# shield_v2.net
KiCad netlist of a schematic drawn in EAGLE
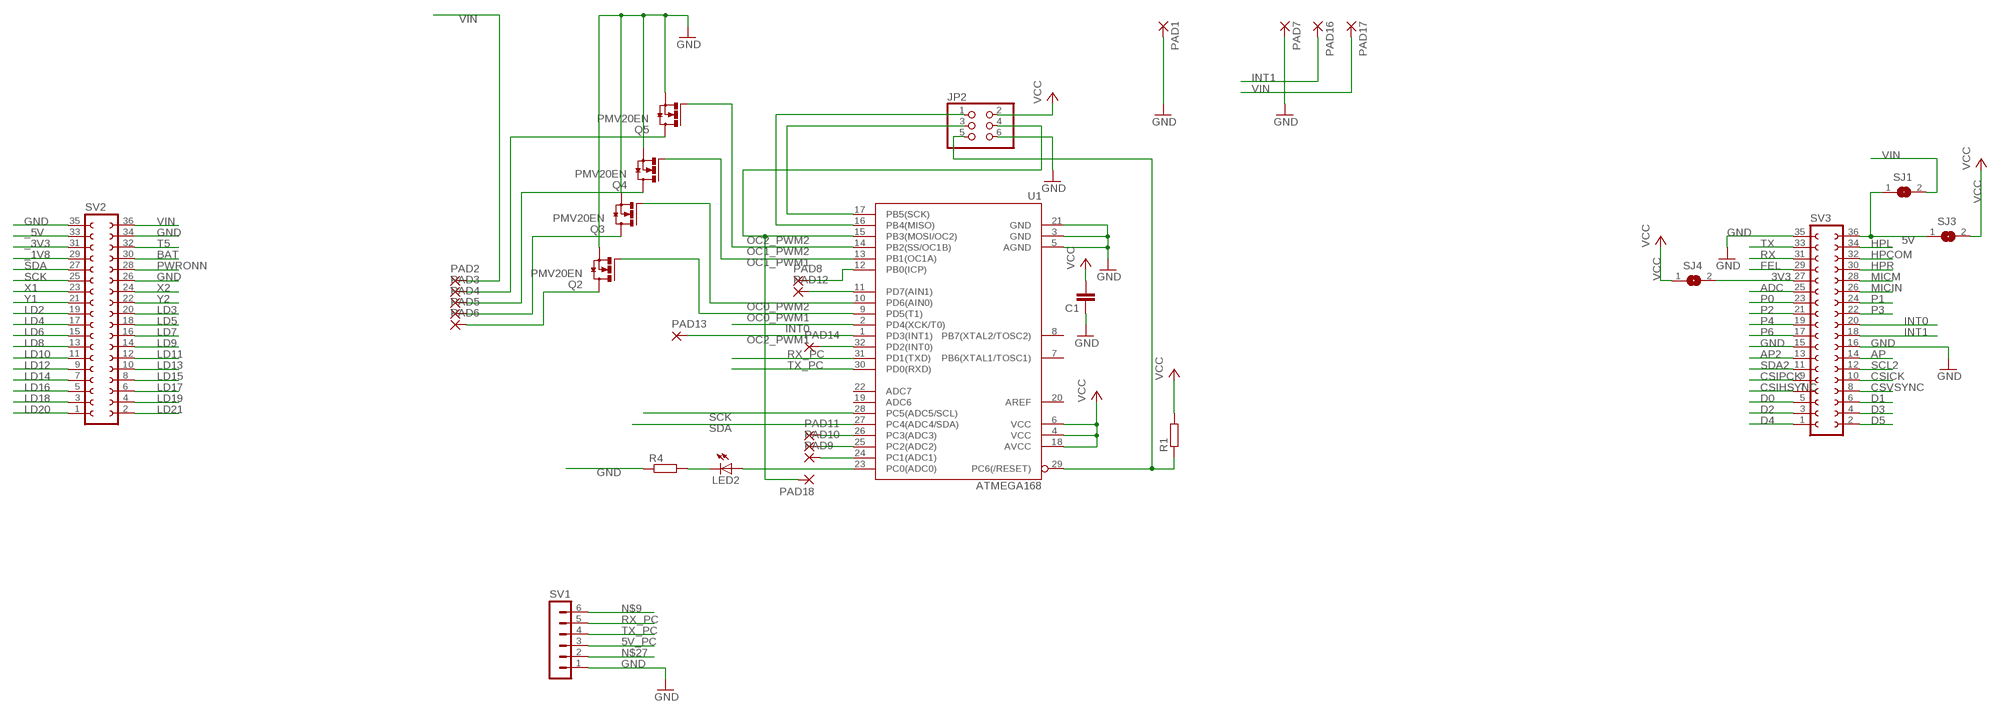
[diagram p0: schematic, sheet 1]

(export (version "E")
  (design (tool "Eeschema 10.0.6"))
  (components
    (comp (ref "C1")
      (value "C-EUC0805")
      (footprint "eagle-import:C0805")
      (libsource (lib "eagle-import") (part "C-EUC0805"))
    )
    (comp (ref "JP2")
      (value "PINHD-2X3")
      (footprint "eagle-import:2X03")
      (libsource (lib "eagle-import") (part "PINHD-2X3"))
    )
    (comp (ref "LED2")
      (value "LEDCHIP-LED0805")
      (footprint "eagle-import:CHIP-LED0805")
      (libsource (lib "eagle-import") (part "LEDCHIP-LED0805"))
    )
    (comp (ref "PAD1")
      (value "3,17/1,3")
      (footprint "eagle-import:3,17_1,3")
      (libsource (lib "eagle-import") (part "3,17/1,3"))
    )
    (comp (ref "PAD2")
      (value "3,17/1,3")
      (footprint "eagle-import:3,17_1,3")
      (libsource (lib "eagle-import") (part "3,17/1,3"))
    )
    (comp (ref "PAD3")
      (value "3,17/1,3")
      (footprint "eagle-import:3,17_1,3")
      (libsource (lib "eagle-import") (part "3,17/1,3"))
    )
    (comp (ref "PAD4")
      (value "3,17/1,3")
      (footprint "eagle-import:3,17_1,3")
      (libsource (lib "eagle-import") (part "3,17/1,3"))
    )
    (comp (ref "PAD5")
      (value "3,17/1,3")
      (footprint "eagle-import:3,17_1,3")
      (libsource (lib "eagle-import") (part "3,17/1,3"))
    )
    (comp (ref "PAD6")
      (value "3,17/1,3")
      (footprint "eagle-import:3,17_1,3")
      (libsource (lib "eagle-import") (part "3,17/1,3"))
    )
    (comp (ref "PAD7")
      (value "3,17/1,3")
      (footprint "eagle-import:3,17_1,3")
      (libsource (lib "eagle-import") (part "3,17/1,3"))
    )
    (comp (ref "PAD8")
      (value "SMD5")
      (footprint "eagle-import:SMD2,54-5,08")
      (libsource (lib "eagle-import") (part "SMD5"))
    )
    (comp (ref "PAD9")
      (value "3,17/1,3")
      (footprint "eagle-import:3,17_1,3")
      (libsource (lib "eagle-import") (part "3,17/1,3"))
    )
    (comp (ref "PAD10")
      (value "3,17/1,3")
      (footprint "eagle-import:3,17_1,3")
      (libsource (lib "eagle-import") (part "3,17/1,3"))
    )
    (comp (ref "PAD11")
      (value "3,17/1,3")
      (footprint "eagle-import:3,17_1,3")
      (libsource (lib "eagle-import") (part "3,17/1,3"))
    )
    (comp (ref "PAD12")
      (value "SMD5")
      (footprint "eagle-import:SMD2,54-5,08")
      (libsource (lib "eagle-import") (part "SMD5"))
    )
    (comp (ref "PAD13")
      (value "SMD2")
      (footprint "eagle-import:SMD1,27-2,54")
      (libsource (lib "eagle-import") (part "SMD2"))
    )
    (comp (ref "PAD14")
      (value "3,17/1,3")
      (footprint "eagle-import:3,17_1,3")
      (libsource (lib "eagle-import") (part "3,17/1,3"))
    )
    (comp (ref "PAD16")
      (value "3,17/1,3")
      (footprint "eagle-import:3,17_1,3")
      (libsource (lib "eagle-import") (part "3,17/1,3"))
    )
    (comp (ref "PAD17")
      (value "3,17/1,3")
      (footprint "eagle-import:3,17_1,3")
      (libsource (lib "eagle-import") (part "3,17/1,3"))
    )
    (comp (ref "PAD18")
      (value "3,17/1,3")
      (footprint "eagle-import:3,17_1,3")
      (libsource (lib "eagle-import") (part "3,17/1,3"))
    )
    (comp (ref "Q2")
      (value "PMV20EN")
      (footprint "eagle-import:SOT223")
      (libsource (lib "eagle-import") (part "NMOSFET_SMD_223"))
    )
    (comp (ref "Q3")
      (value "PMV20EN")
      (footprint "eagle-import:SOT223")
      (libsource (lib "eagle-import") (part "NMOSFET_SMD_223"))
    )
    (comp (ref "Q4")
      (value "PMV20EN")
      (footprint "eagle-import:SOT223")
      (libsource (lib "eagle-import") (part "NMOSFET_SMD_223"))
    )
    (comp (ref "Q5")
      (value "PMV20EN")
      (footprint "eagle-import:SOT223")
      (libsource (lib "eagle-import") (part "NMOSFET_SMD_223"))
    )
    (comp (ref "R1")
      (value "R-EU_M1206")
      (footprint "eagle-import:M1206")
      (libsource (lib "eagle-import") (part "R-EU_M1206"))
    )
    (comp (ref "R4")
      (value "R-EU_M1206")
      (footprint "eagle-import:M1206")
      (libsource (lib "eagle-import") (part "R-EU_M1206"))
    )
    (comp (ref "SJ1") (value "SJ") (footprint "eagle-import:SJ") (libsource (lib "eagle-import") (part "SJ")))
    (comp (ref "SJ3") (value "SJ") (footprint "eagle-import:SJ") (libsource (lib "eagle-import") (part "SJ")))
    (comp (ref "SJ4") (value "SJ") (footprint "eagle-import:SJ") (libsource (lib "eagle-import") (part "SJ")))
    (comp (ref "SV1")
      (value "MA06-1")
      (footprint "eagle-import:MA06-1")
      (libsource (lib "eagle-import") (part "MA06-1"))
    )
    (comp (ref "SV2")
      (value "FE18-2")
      (footprint "eagle-import:FE18-2")
      (libsource (lib "eagle-import") (part "FE18-2"))
    )
    (comp (ref "SV3")
      (value "FE18-2")
      (footprint "eagle-import:FE18-2")
      (libsource (lib "eagle-import") (part "FE18-2"))
    )
    (comp (ref "U1")
      (value "ATMEGA168")
      (footprint "eagle-import:TQFP32-08")
      (libsource (lib "eagle-import") (part "ATMEGA168"))
    )
  )
  (nets
    (net (code "1") (name "/3V3") (class "Default")
      (node (ref "SJ4") (pin "2") (pinfunction "2_2") (pintype "passive"))
      (node (ref "SV3") (pin "27") (pinfunction "27_27") (pintype "passive"))
    )
    (net (code "2") (name "/5V") (class "Default")
      (node (ref "SJ1") (pin "1") (pinfunction "1_1") (pintype "passive"))
      (node (ref "SJ3") (pin "1") (pinfunction "1_1") (pintype "passive"))
      (node (ref "SV3") (pin "36") (pinfunction "36_36") (pintype "passive"))
    )
    (net (code "3") (name "/5V_PC") (class "Default")
      (node (ref "SV1") (pin "3") (pinfunction "3_3") (pintype "passive"))
    )
    (net (code "4") (name "/ADC") (class "Default")
      (node (ref "SV3") (pin "25") (pinfunction "25_25") (pintype "passive"))
    )
    (net (code "5") (name "/AP") (class "Default")
      (node (ref "SV3") (pin "14") (pinfunction "14_14") (pintype "passive"))
    )
    (net (code "6") (name "/AP2") (class "Default")
      (node (ref "SV3") (pin "13") (pinfunction "13_13") (pintype "passive"))
    )
    (net (code "7") (name "/BAT") (class "Default")
      (node (ref "SV2") (pin "30") (pinfunction "30_30") (pintype "passive"))
    )
    (net (code "8") (name "/CSICK") (class "Default")
      (node (ref "SV3") (pin "10") (pinfunction "10_10") (pintype "passive"))
    )
    (net (code "9") (name "/CSIHSYNC") (class "Default")
      (node (ref "SV3") (pin "7") (pinfunction "7_7") (pintype "passive"))
    )
    (net (code "10") (name "/CSIPCK") (class "Default")
      (node (ref "SV3") (pin "9") (pinfunction "9_9") (pintype "passive"))
    )
    (net (code "11") (name "/CSVSYNC") (class "Default")
      (node (ref "SV3") (pin "8") (pinfunction "8_8") (pintype "passive"))
    )
    (net (code "12") (name "/D0") (class "Default")
      (node (ref "SV3") (pin "5") (pinfunction "5_5") (pintype "passive"))
    )
    (net (code "13") (name "/D1") (class "Default")
      (node (ref "SV3") (pin "6") (pinfunction "6_6") (pintype "passive"))
    )
    (net (code "14") (name "/D2") (class "Default")
      (node (ref "SV3") (pin "3") (pinfunction "3_3") (pintype "passive"))
    )
    (net (code "15") (name "/D3") (class "Default")
      (node (ref "SV3") (pin "4") (pinfunction "4_4") (pintype "passive"))
    )
    (net (code "16") (name "/D4") (class "Default")
      (node (ref "SV3") (pin "1") (pinfunction "1_1") (pintype "passive"))
    )
    (net (code "17") (name "/D5") (class "Default")
      (node (ref "SV3") (pin "2") (pinfunction "2_2") (pintype "passive"))
    )
    (net (code "18") (name "/FEL") (class "Default")
      (node (ref "SV3") (pin "29") (pinfunction "29_29") (pintype "passive"))
    )
    (net (code "19") (name "/HPCOM") (class "Default")
      (node (ref "SV3") (pin "32") (pinfunction "32_32") (pintype "passive"))
    )
    (net (code "20") (name "/HPL") (class "Default")
      (node (ref "SV3") (pin "34") (pinfunction "34_34") (pintype "passive"))
    )
    (net (code "21") (name "/HPR") (class "Default")
      (node (ref "SV3") (pin "30") (pinfunction "30_30") (pintype "passive"))
    )
    (net (code "22") (name "/INT0") (class "Default")
      (node (ref "SV3") (pin "20") (pinfunction "20_20") (pintype "passive"))
      (node (ref "U1") (pin "2") (pinfunction "PD4(XCK/T0)_2") (pintype "bidirectional"))
    )
    (net (code "23") (name "/INT1") (class "Default")
      (node (ref "PAD16") (pin "1") (pinfunction "P_1") (pintype "passive"))
      (node (ref "SV3") (pin "18") (pinfunction "18_18") (pintype "passive"))
    )
    (net (code "24") (name "/LD2") (class "Default")
      (node (ref "SV2") (pin "19") (pinfunction "19_19") (pintype "passive"))
    )
    (net (code "25") (name "/LD3") (class "Default")
      (node (ref "SV2") (pin "20") (pinfunction "20_20") (pintype "passive"))
    )
    (net (code "26") (name "/LD4") (class "Default")
      (node (ref "SV2") (pin "17") (pinfunction "17_17") (pintype "passive"))
    )
    (net (code "27") (name "/LD5") (class "Default")
      (node (ref "SV2") (pin "18") (pinfunction "18_18") (pintype "passive"))
    )
    (net (code "28") (name "/LD6") (class "Default")
      (node (ref "SV2") (pin "15") (pinfunction "15_15") (pintype "passive"))
    )
    (net (code "29") (name "/LD7") (class "Default")
      (node (ref "SV2") (pin "16") (pinfunction "16_16") (pintype "passive"))
    )
    (net (code "30") (name "/LD8") (class "Default")
      (node (ref "SV2") (pin "13") (pinfunction "13_13") (pintype "passive"))
    )
    (net (code "31") (name "/LD9") (class "Default")
      (node (ref "SV2") (pin "14") (pinfunction "14_14") (pintype "passive"))
    )
    (net (code "32") (name "/LD10") (class "Default")
      (node (ref "SV2") (pin "11") (pinfunction "11_11") (pintype "passive"))
    )
    (net (code "33") (name "/LD11") (class "Default")
      (node (ref "SV2") (pin "12") (pinfunction "12_12") (pintype "passive"))
    )
    (net (code "34") (name "/LD12") (class "Default")
      (node (ref "SV2") (pin "9") (pinfunction "9_9") (pintype "passive"))
    )
    (net (code "35") (name "/LD13") (class "Default")
      (node (ref "SV2") (pin "10") (pinfunction "10_10") (pintype "passive"))
    )
    (net (code "36") (name "/LD14") (class "Default")
      (node (ref "SV2") (pin "7") (pinfunction "7_7") (pintype "passive"))
    )
    (net (code "37") (name "/LD15") (class "Default")
      (node (ref "SV2") (pin "8") (pinfunction "8_8") (pintype "passive"))
    )
    (net (code "38") (name "/LD16") (class "Default")
      (node (ref "SV2") (pin "5") (pinfunction "5_5") (pintype "passive"))
    )
    (net (code "39") (name "/LD17") (class "Default")
      (node (ref "SV2") (pin "6") (pinfunction "6_6") (pintype "passive"))
    )
    (net (code "40") (name "/LD18") (class "Default")
      (node (ref "SV2") (pin "3") (pinfunction "3_3") (pintype "passive"))
    )
    (net (code "41") (name "/LD19") (class "Default")
      (node (ref "SV2") (pin "4") (pinfunction "4_4") (pintype "passive"))
    )
    (net (code "42") (name "/LD20") (class "Default")
      (node (ref "SV2") (pin "1") (pinfunction "1_1") (pintype "passive"))
    )
    (net (code "43") (name "/LD21") (class "Default")
      (node (ref "SV2") (pin "2") (pinfunction "2_2") (pintype "passive"))
    )
    (net (code "44") (name "/MICIN") (class "Default")
      (node (ref "SV3") (pin "26") (pinfunction "26_26") (pintype "passive"))
    )
    (net (code "45") (name "/MICM") (class "Default")
      (node (ref "SV3") (pin "28") (pinfunction "28_28") (pintype "passive"))
    )
    (net (code "46") (name "/N$9") (class "Default")
      (node (ref "SV1") (pin "6") (pinfunction "6_6") (pintype "passive"))
    )
    (net (code "47") (name "/N$27") (class "Default")
      (node (ref "SV1") (pin "2") (pinfunction "2_2") (pintype "passive"))
    )
    (net (code "48") (name "/OC0_PWM1") (class "Default")
      (node (ref "Q2") (pin "1") (pinfunction "G_1") (pintype "passive"))
      (node (ref "U1") (pin "9") (pinfunction "PD5(T1)_9") (pintype "bidirectional"))
    )
    (net (code "49") (name "/OC0_PWM2") (class "Default")
      (node (ref "Q3") (pin "1") (pinfunction "G_1") (pintype "passive"))
      (node (ref "U1") (pin "10") (pinfunction "PD6(AIN0)_10") (pintype "bidirectional"))
    )
    (net (code "50") (name "/OC1_PWM1") (class "Default")
      (node (ref "Q4") (pin "1") (pinfunction "G_1") (pintype "passive"))
      (node (ref "U1") (pin "13") (pinfunction "PB1(OC1A)_13") (pintype "bidirectional"))
    )
    (net (code "51") (name "/OC1_PWM2") (class "Default")
      (node (ref "Q5") (pin "1") (pinfunction "G_1") (pintype "passive"))
      (node (ref "U1") (pin "14") (pinfunction "PB2(SS/OC1B)_14") (pintype "bidirectional"))
    )
    (net (code "52") (name "/OC2_PWM1") (class "Default")
      (node (ref "PAD13") (pin "1") (pinfunction "P_1") (pintype "passive"))
      (node (ref "U1") (pin "1") (pinfunction "PD3(INT1)_1") (pintype "bidirectional"))
    )
    (net (code "53") (name "/OC2_PWM2") (class "Default")
      (node (ref "JP2") (pin "4") (pinfunction "4_4") (pintype "passive"))
      (node (ref "PAD18") (pin "1") (pinfunction "P_1") (pintype "passive"))
      (node (ref "U1") (pin "15") (pinfunction "PB3(MOSI/OC2)_15") (pintype "bidirectional"))
    )
    (net (code "54") (name "/P0") (class "Default")
      (node (ref "SV3") (pin "23") (pinfunction "23_23") (pintype "passive"))
    )
    (net (code "55") (name "/P1") (class "Default")
      (node (ref "SV3") (pin "24") (pinfunction "24_24") (pintype "passive"))
    )
    (net (code "56") (name "/P2") (class "Default")
      (node (ref "SV3") (pin "21") (pinfunction "21_21") (pintype "passive"))
    )
    (net (code "57") (name "/P3") (class "Default")
      (node (ref "SV3") (pin "22") (pinfunction "22_22") (pintype "passive"))
    )
    (net (code "58") (name "/P4") (class "Default")
      (node (ref "SV3") (pin "19") (pinfunction "19_19") (pintype "passive"))
    )
    (net (code "59") (name "/P6") (class "Default")
      (node (ref "SV3") (pin "17") (pinfunction "17_17") (pintype "passive"))
    )
    (net (code "60") (name "/PWRONN") (class "Default")
      (node (ref "SV2") (pin "28") (pinfunction "28_28") (pintype "passive"))
    )
    (net (code "61") (name "/RX") (class "Default")
      (node (ref "SV3") (pin "31") (pinfunction "31_31") (pintype "passive"))
    )
    (net (code "62") (name "/RX_PC") (class "Default")
      (node (ref "SV1") (pin "5") (pinfunction "5_5") (pintype "passive"))
      (node (ref "U1") (pin "31") (pinfunction "PD1(TXD)_31") (pintype "bidirectional"))
    )
    (net (code "63") (name "/SCK") (class "Default")
      (node (ref "SV2") (pin "25") (pinfunction "25_25") (pintype "passive"))
      (node (ref "U1") (pin "28") (pinfunction "PC5(ADC5/SCL)_28") (pintype "bidirectional"))
    )
    (net (code "64") (name "/SCL2") (class "Default")
      (node (ref "SV3") (pin "12") (pinfunction "12_12") (pintype "passive"))
    )
    (net (code "65") (name "/SDA") (class "Default")
      (node (ref "SV2") (pin "27") (pinfunction "27_27") (pintype "passive"))
      (node (ref "U1") (pin "27") (pinfunction "PC4(ADC4/SDA)_27") (pintype "bidirectional"))
    )
    (net (code "66") (name "/SDA2") (class "Default")
      (node (ref "SV3") (pin "11") (pinfunction "11_11") (pintype "passive"))
    )
    (net (code "67") (name "/T5") (class "Default")
      (node (ref "SV2") (pin "32") (pinfunction "32_32") (pintype "passive"))
    )
    (net (code "68") (name "/TX") (class "Default")
      (node (ref "SV3") (pin "33") (pinfunction "33_33") (pintype "passive"))
    )
    (net (code "69") (name "/TX_PC") (class "Default")
      (node (ref "SV1") (pin "4") (pinfunction "4_4") (pintype "passive"))
      (node (ref "U1") (pin "30") (pinfunction "PD0(RXD)_30") (pintype "bidirectional"))
    )
    (net (code "70") (name "/VIN") (class "Default")
      (node (ref "PAD17") (pin "1") (pinfunction "P_1") (pintype "passive"))
      (node (ref "PAD2") (pin "1") (pinfunction "P_1") (pintype "passive"))
      (node (ref "SJ1") (pin "2") (pinfunction "2_2") (pintype "passive"))
      (node (ref "SV2") (pin "36") (pinfunction "36_36") (pintype "passive"))
    )
    (net (code "71") (name "/X1") (class "Default")
      (node (ref "SV2") (pin "23") (pinfunction "23_23") (pintype "passive"))
    )
    (net (code "72") (name "/X2") (class "Default")
      (node (ref "SV2") (pin "24") (pinfunction "24_24") (pintype "passive"))
    )
    (net (code "73") (name "/Y1") (class "Default")
      (node (ref "SV2") (pin "21") (pinfunction "21_21") (pintype "passive"))
    )
    (net (code "74") (name "/Y2") (class "Default")
      (node (ref "SV2") (pin "22") (pinfunction "22_22") (pintype "passive"))
    )
    (net (code "75") (name "/_1V8") (class "Default")
      (node (ref "SV2") (pin "29") (pinfunction "29_29") (pintype "passive"))
    )
    (net (code "76") (name "/_3V3") (class "Default")
      (node (ref "SV2") (pin "31") (pinfunction "31_31") (pintype "passive"))
    )
    (net (code "77") (name "/_5V") (class "Default")
      (node (ref "SV2") (pin "33") (pinfunction "33_33") (pintype "passive"))
    )
    (net (code "78") (name "GND") (class "Default")
      (node (ref "C1") (pin "1") (pinfunction "1_1") (pintype "passive"))
      (node (ref "JP2") (pin "6") (pinfunction "6_6") (pintype "passive"))
      (node (ref "PAD1") (pin "1") (pinfunction "P_1") (pintype "passive"))
      (node (ref "PAD7") (pin "1") (pinfunction "P_1") (pintype "passive"))
      (node (ref "Q2") (pin "3") (pinfunction "S_3") (pintype "passive"))
      (node (ref "Q3") (pin "3") (pinfunction "S_3") (pintype "passive"))
      (node (ref "Q4") (pin "3") (pinfunction "S_3") (pintype "passive"))
      (node (ref "Q5") (pin "3") (pinfunction "S_3") (pintype "passive"))
      (node (ref "R4") (pin "1") (pinfunction "1_1") (pintype "passive"))
      (node (ref "SV1") (pin "1") (pinfunction "1_1") (pintype "passive"))
      (node (ref "SV2") (pin "26") (pinfunction "26_26") (pintype "passive"))
      (node (ref "SV2") (pin "34") (pinfunction "34_34") (pintype "passive"))
      (node (ref "SV2") (pin "35") (pinfunction "35_35") (pintype "passive"))
      (node (ref "SV3") (pin "15") (pinfunction "15_15") (pintype "passive"))
      (node (ref "SV3") (pin "16") (pinfunction "16_16") (pintype "passive"))
      (node (ref "SV3") (pin "35") (pinfunction "35_35") (pintype "passive"))
      (node (ref "U1") (pin "21") (pinfunction "GND_21") (pintype "bidirectional"))
      (node (ref "U1") (pin "3") (pinfunction "GND_3") (pintype "bidirectional"))
      (node (ref "U1") (pin "5") (pinfunction "AGND_5") (pintype "bidirectional"))
    )
    (net (code "79") (name "Net-(LED2-PadC)") (class "Default")
      (node (ref "LED2") (pin "C") (pinfunction "C_C") (pintype "passive"))
      (node (ref "R4") (pin "2") (pinfunction "2_2") (pintype "passive"))
    )
    (net (code "80") (name "Net-(PAD3-P)") (class "Default")
      (node (ref "PAD3") (pin "1") (pinfunction "P_1") (pintype "passive"))
      (node (ref "Q5") (pin "2") (pinfunction "D_2") (pintype "passive"))
      (node (ref "Q5") (pin "4") (pinfunction "D_4") (pintype "passive"))
    )
    (net (code "81") (name "Net-(PAD4-P)") (class "Default")
      (node (ref "PAD4") (pin "1") (pinfunction "P_1") (pintype "passive"))
      (node (ref "Q4") (pin "2") (pinfunction "D_2") (pintype "passive"))
      (node (ref "Q4") (pin "4") (pinfunction "D_4") (pintype "passive"))
    )
    (net (code "82") (name "Net-(PAD5-P)") (class "Default")
      (node (ref "PAD5") (pin "1") (pinfunction "P_1") (pintype "passive"))
      (node (ref "Q3") (pin "2") (pinfunction "D_2") (pintype "passive"))
      (node (ref "Q3") (pin "4") (pinfunction "D_4") (pintype "passive"))
    )
    (net (code "83") (name "Net-(PAD6-P)") (class "Default")
      (node (ref "PAD6") (pin "1") (pinfunction "P_1") (pintype "passive"))
      (node (ref "Q2") (pin "2") (pinfunction "D_2") (pintype "passive"))
      (node (ref "Q2") (pin "4") (pinfunction "D_4") (pintype "passive"))
    )
    (net (code "84") (name "Net-(PAD8-P)") (class "Default")
      (node (ref "PAD8") (pin "1") (pinfunction "P_1") (pintype "passive"))
      (node (ref "U1") (pin "12") (pinfunction "PB0(ICP)_12") (pintype "bidirectional"))
    )
    (net (code "85") (name "Net-(PAD9-P)") (class "Default")
      (node (ref "PAD9") (pin "1") (pinfunction "P_1") (pintype "passive"))
      (node (ref "U1") (pin "24") (pinfunction "PC1(ADC1)_24") (pintype "bidirectional"))
    )
    (net (code "86") (name "Net-(PAD10-P)") (class "Default")
      (node (ref "PAD10") (pin "1") (pinfunction "P_1") (pintype "passive"))
      (node (ref "U1") (pin "25") (pinfunction "PC2(ADC2)_25") (pintype "bidirectional"))
    )
    (net (code "87") (name "Net-(PAD11-P)") (class "Default")
      (node (ref "PAD11") (pin "1") (pinfunction "P_1") (pintype "passive"))
      (node (ref "U1") (pin "26") (pinfunction "PC3(ADC3)_26") (pintype "bidirectional"))
    )
    (net (code "88") (name "Net-(PAD12-P)") (class "Default")
      (node (ref "PAD12") (pin "1") (pinfunction "P_1") (pintype "passive"))
      (node (ref "U1") (pin "11") (pinfunction "PD7(AIN1)_11") (pintype "bidirectional"))
    )
    (net (code "89") (name "Net-(PAD14-P)") (class "Default")
      (node (ref "PAD14") (pin "1") (pinfunction "P_1") (pintype "passive"))
      (node (ref "U1") (pin "32") (pinfunction "PD2(INT0)_32") (pintype "bidirectional"))
    )
    (net (code "90") (name "Net-(U1-PB4(MISO))") (class "Default")
      (node (ref "JP2") (pin "1") (pinfunction "1_1") (pintype "passive"))
      (node (ref "U1") (pin "16") (pinfunction "PB4(MISO)_16") (pintype "bidirectional"))
    )
    (net (code "91") (name "Net-(U1-PB5(SCK))") (class "Default")
      (node (ref "JP2") (pin "3") (pinfunction "3_3") (pintype "passive"))
      (node (ref "U1") (pin "17") (pinfunction "PB5(SCK)_17") (pintype "bidirectional"))
    )
    (net (code "92") (name "Net-(U1-PC0(ADC0))") (class "Default")
      (node (ref "LED2") (pin "A") (pinfunction "A_A") (pintype "passive"))
      (node (ref "U1") (pin "23") (pinfunction "PC0(ADC0)_23") (pintype "bidirectional"))
    )
    (net (code "93") (name "Net-(U1-PC6({slash}RESET))") (class "Default")
      (node (ref "JP2") (pin "5") (pinfunction "5_5") (pintype "passive"))
      (node (ref "R1") (pin "1") (pinfunction "1_1") (pintype "passive"))
      (node (ref "U1") (pin "29") (pinfunction "PC6(/RESET)_29") (pintype "bidirectional"))
    )
    (net (code "94") (name "VCC") (class "Default")
      (node (ref "C1") (pin "2") (pinfunction "2_2") (pintype "passive"))
      (node (ref "JP2") (pin "2") (pinfunction "2_2") (pintype "passive"))
      (node (ref "R1") (pin "2") (pinfunction "2_2") (pintype "passive"))
      (node (ref "SJ3") (pin "2") (pinfunction "2_2") (pintype "passive"))
      (node (ref "SJ4") (pin "1") (pinfunction "1_1") (pintype "passive"))
      (node (ref "U1") (pin "18") (pinfunction "AVCC_18") (pintype "bidirectional"))
      (node (ref "U1") (pin "4") (pinfunction "VCC_4") (pintype "bidirectional"))
      (node (ref "U1") (pin "6") (pinfunction "VCC_6") (pintype "bidirectional"))
    )
    (net (code "95") (name "unconnected-(U1-ADC6-Pad19)") (class "Default")
      (node (ref "U1") (pin "19") (pinfunction "ADC6_19") (pintype "bidirectional"))
    )
    (net (code "96") (name "unconnected-(U1-ADC7-Pad22)") (class "Default")
      (node (ref "U1") (pin "22") (pinfunction "ADC7_22") (pintype "bidirectional"))
    )
    (net (code "97") (name "unconnected-(U1-AREF-Pad20)") (class "Default")
      (node (ref "U1") (pin "20") (pinfunction "AREF_20") (pintype "bidirectional"))
    )
    (net (code "98") (name "unconnected-(U1-PB6(XTAL1{slash}TOSC1)-Pad7)") (class "Default")
      (node (ref "U1") (pin "7") (pinfunction "PB6(XTAL1/TOSC1)_7") (pintype "bidirectional"))
    )
    (net (code "99") (name "unconnected-(U1-PB7(XTAL2{slash}TOSC2)-Pad8)") (class "Default")
      (node (ref "U1") (pin "8") (pinfunction "PB7(XTAL2/TOSC2)_8") (pintype "bidirectional"))
    )
  )
)
